# Drop_Screen_OCT_2022_Drivers_1.net
KiCad netlist of a schematic drawn in EasyEDA
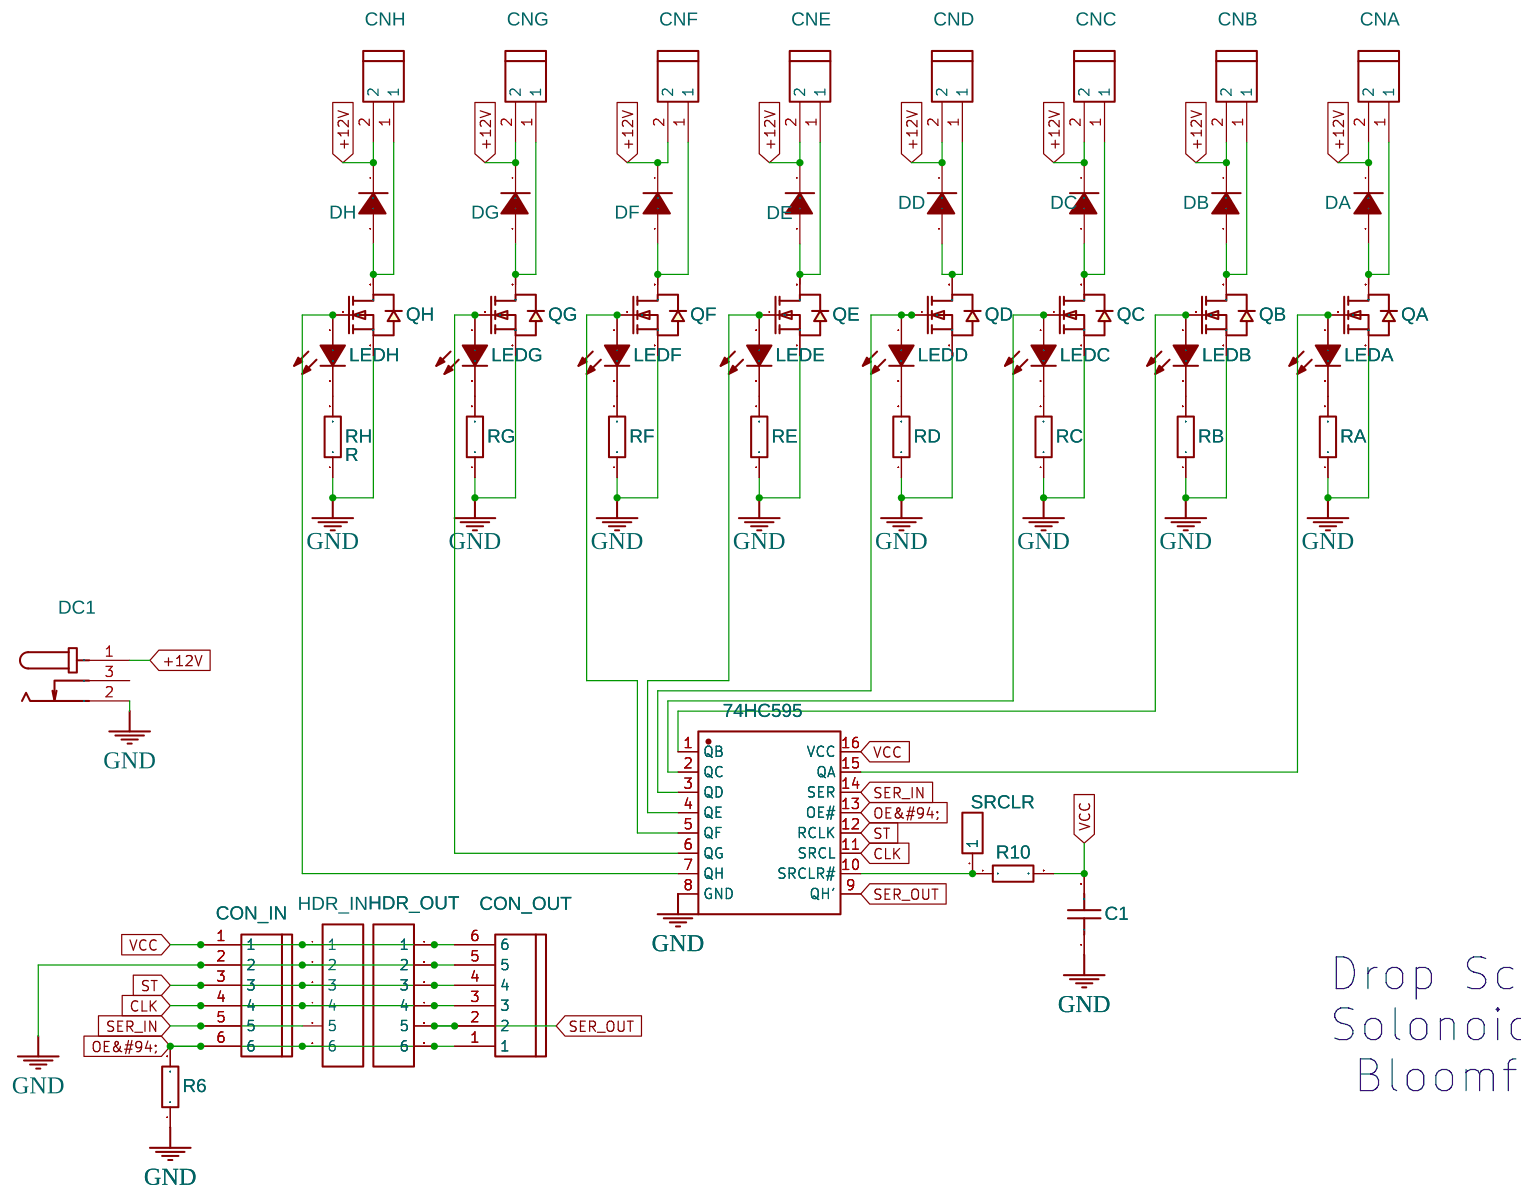
[diagram p0: schematic sheet]

(export (version "E")
  (design (tool "Eeschema 10.0.6"))
  (components
    (comp (ref "C1")
      (value "C")
      (fields
        (field (name "BOM_Manufacturer Part") "CC0603KRX7R7BB104")
        (field (name "BOM_Supplier Part") "C108079")
      )
      (libsource (lib "") (part "CC0603KRX7R7BB104"))
    )
    (comp (ref "CNA")
      (value "CON")
      (fields (field (name "BOM_Manufacturer Part") "XH-2AW") (field (name "BOM_Supplier Part") "C33132"))
      (libsource (lib "") (part "XH-2AW_2"))
    )
    (comp (ref "CNB")
      (value "CON")
      (fields (field (name "BOM_Manufacturer Part") "XH-2AW") (field (name "BOM_Supplier Part") "C33132"))
      (libsource (lib "") (part "XH-2AW_7"))
    )
    (comp (ref "CNC")
      (value "CON")
      (fields (field (name "BOM_Manufacturer Part") "XH-2AW") (field (name "BOM_Supplier Part") "C33132"))
      (libsource (lib "") (part "XH-2AW_5"))
    )
    (comp (ref "CND")
      (value "CON")
      (fields (field (name "BOM_Manufacturer Part") "XH-2AW") (field (name "BOM_Supplier Part") "C33132"))
      (libsource (lib "") (part "XH-2AW_4"))
    )
    (comp (ref "CNE")
      (value "CON")
      (fields (field (name "BOM_Manufacturer Part") "XH-2AW") (field (name "BOM_Supplier Part") "C33132"))
      (libsource (lib "") (part "XH-2AW_6"))
    )
    (comp (ref "CNF")
      (value "CON")
      (fields (field (name "BOM_Manufacturer Part") "XH-2AW") (field (name "BOM_Supplier Part") "C33132"))
      (libsource (lib "") (part "XH-2AW_3"))
    )
    (comp (ref "CNG")
      (value "CON")
      (fields (field (name "BOM_Manufacturer Part") "XH-2AW") (field (name "BOM_Supplier Part") "C33132"))
      (libsource (lib "") (part "XH-2AW_1"))
    )
    (comp (ref "CNH")
      (value "CON")
      (fields (field (name "BOM_Manufacturer Part") "XH-2AW") (field (name "BOM_Supplier Part") "C33132"))
      (libsource (lib "") (part "XH-2AW"))
    )
    (comp (ref "CON_IN")
      (value "CON6")
      (fields (field (name "BOM_Manufacturer Part") "XH-6AW") (field (name "BOM_Supplier Part") "C8876"))
      (libsource (lib "") (part "XH-6AW_C8876_1"))
    )
    (comp (ref "CON_OUT")
      (value "CON6")
      (fields (field (name "BOM_Manufacturer Part") "XH-6AW") (field (name "BOM_Supplier Part") "C8876"))
      (libsource (lib "") (part "XH-6AW_C8876"))
    )
    (comp (ref "DA")
      (value "D")
      (fields (field (name "BOM_Manufacturer Part") "1N4007F") (field (name "BOM_Supplier Part") "C110856"))
      (libsource (lib "") (part "1N4007F_6"))
    )
    (comp (ref "DB")
      (value "D")
      (fields (field (name "BOM_Manufacturer Part") "1N4007F") (field (name "BOM_Supplier Part") "C110856"))
      (libsource (lib "") (part "1N4007F_5"))
    )
    (comp (ref "DC")
      (value "D")
      (fields (field (name "BOM_Manufacturer Part") "1N4007F") (field (name "BOM_Supplier Part") "C110856"))
      (libsource (lib "") (part "1N4007F_7"))
    )
    (comp (ref "DC1")
      (value "DC")
      (fields
        (field (name "BOM_Manufacturer Part") "DC005-2.0MM")
        (field (name "BOM_Supplier Part") "C111567")
      )
      (libsource (lib "") (part "DC005-2.0MM"))
    )
    (comp (ref "DD")
      (value "D")
      (fields (field (name "BOM_Manufacturer Part") "1N4007F") (field (name "BOM_Supplier Part") "C110856"))
      (libsource (lib "") (part "1N4007F_2"))
    )
    (comp (ref "DE")
      (value "D")
      (fields (field (name "BOM_Manufacturer Part") "1N4007F") (field (name "BOM_Supplier Part") "C110856"))
      (libsource (lib "") (part "1N4007F_3"))
    )
    (comp (ref "DF")
      (value "D")
      (fields (field (name "BOM_Manufacturer Part") "1N4007F") (field (name "BOM_Supplier Part") "C110856"))
      (libsource (lib "") (part "1N4007F_4"))
    )
    (comp (ref "DG")
      (value "D")
      (fields (field (name "BOM_Manufacturer Part") "1N4007F") (field (name "BOM_Supplier Part") "C110856"))
      (libsource (lib "") (part "1N4007F"))
    )
    (comp (ref "DH")
      (value "D")
      (fields (field (name "BOM_Manufacturer Part") "1N4007F") (field (name "BOM_Supplier Part") "C110856"))
      (libsource (lib "") (part "1N4007F_1"))
    )
    (comp (ref "HDR_IN")
      (value "HDR6")
      (fields (field (name "BOM_Supplier Part") "C190819"))
      (libsource (lib "") (part "HDR-M-2.54_1x6_1"))
    )
    (comp (ref "HDR_OUT")
      (value "HDR6")
      (fields (field (name "BOM_Supplier Part") "C190819"))
      (libsource (lib "") (part "HDR-M-2.54_1x6"))
    )
    (comp (ref "IC2")
      (value "74HC595")
      (fields
        (field (name "BOM_Manufacturer Part") "U74HC595AG-S16-R")
        (field (name "BOM_Supplier Part") "C87300")
      )
      (libsource (lib "") (part "U74HC595AG-S16-R"))
    )
    (comp (ref "LEDA")
      (value "LED")
      (fields
        (field (name "BOM_Manufacturer Part") "19-217/BHC-ZL1M2RY/3T")
        (field (name "BOM_Supplier Part") "C72041")
      )
      (libsource (lib "") (part "19-217/BHC-ZL1M2RY/3T_7"))
    )
    (comp (ref "LEDB")
      (value "LED")
      (fields
        (field (name "BOM_Manufacturer Part") "19-217/BHC-ZL1M2RY/3T")
        (field (name "BOM_Supplier Part") "C72041")
      )
      (libsource (lib "") (part "19-217/BHC-ZL1M2RY/3T_3"))
    )
    (comp (ref "LEDC")
      (value "LED")
      (fields
        (field (name "BOM_Manufacturer Part") "19-217/BHC-ZL1M2RY/3T")
        (field (name "BOM_Supplier Part") "C72041")
      )
      (libsource (lib "") (part "19-217/BHC-ZL1M2RY/3T_6"))
    )
    (comp (ref "LEDD")
      (value "LED")
      (fields
        (field (name "BOM_Manufacturer Part") "19-217/BHC-ZL1M2RY/3T")
        (field (name "BOM_Supplier Part") "C72041")
      )
      (libsource (lib "") (part "19-217/BHC-ZL1M2RY/3T"))
    )
    (comp (ref "LEDE")
      (value "LED")
      (fields
        (field (name "BOM_Manufacturer Part") "19-217/BHC-ZL1M2RY/3T")
        (field (name "BOM_Supplier Part") "C72041")
      )
      (libsource (lib "") (part "19-217/BHC-ZL1M2RY/3T_1"))
    )
    (comp (ref "LEDF")
      (value "LED")
      (fields
        (field (name "BOM_Manufacturer Part") "19-217/BHC-ZL1M2RY/3T")
        (field (name "BOM_Supplier Part") "C72041")
      )
      (libsource (lib "") (part "19-217/BHC-ZL1M2RY/3T_2"))
    )
    (comp (ref "LEDG")
      (value "LED")
      (fields
        (field (name "BOM_Manufacturer Part") "19-217/BHC-ZL1M2RY/3T")
        (field (name "BOM_Supplier Part") "C72041")
      )
      (libsource (lib "") (part "19-217/BHC-ZL1M2RY/3T_5"))
    )
    (comp (ref "LEDH")
      (value "LED")
      (fields
        (field (name "BOM_Manufacturer Part") "19-217/BHC-ZL1M2RY/3T")
        (field (name "BOM_Supplier Part") "C72041")
      )
      (libsource (lib "") (part "19-217/BHC-ZL1M2RY/3T_4"))
    )
    (comp (ref "QA")
      (value "Q")
      (fields (field (name "BOM_Manufacturer Part") "JSM2302") (field (name "BOM_Supplier Part") "C916403"))
      (libsource (lib "") (part "JSM2302"))
    )
    (comp (ref "QB")
      (value "Q")
      (fields (field (name "BOM_Manufacturer Part") "JSM2302") (field (name "BOM_Supplier Part") "C916403"))
      (libsource (lib "") (part "JSM2302_5"))
    )
    (comp (ref "QC")
      (value "Q")
      (fields (field (name "BOM_Manufacturer Part") "JSM2302") (field (name "BOM_Supplier Part") "C916403"))
      (libsource (lib "") (part "JSM2302_6"))
    )
    (comp (ref "QD")
      (value "Q")
      (fields (field (name "BOM_Manufacturer Part") "JSM2302") (field (name "BOM_Supplier Part") "C916403"))
      (libsource (lib "") (part "JSM2302_1"))
    )
    (comp (ref "QE")
      (value "Q")
      (fields (field (name "BOM_Manufacturer Part") "JSM2302") (field (name "BOM_Supplier Part") "C916403"))
      (libsource (lib "") (part "JSM2302_2"))
    )
    (comp (ref "QF")
      (value "Q")
      (fields (field (name "BOM_Manufacturer Part") "JSM2302") (field (name "BOM_Supplier Part") "C916403"))
      (libsource (lib "") (part "JSM2302_4"))
    )
    (comp (ref "QG")
      (value "Q")
      (fields (field (name "BOM_Manufacturer Part") "JSM2302") (field (name "BOM_Supplier Part") "C916403"))
      (libsource (lib "") (part "JSM2302_3"))
    )
    (comp (ref "QH")
      (value "Q")
      (fields (field (name "BOM_Manufacturer Part") "JSM2302") (field (name "BOM_Supplier Part") "C916403"))
      (libsource (lib "") (part "JSM2302_7"))
    )
    (comp (ref "R6")
      (value "R")
      (fields
        (field (name "BOM_Manufacturer Part") "0603WAF1001T5E")
        (field (name "BOM_Supplier Part") "C21190")
      )
      (libsource (lib "") (part "0603WAF1001T5E_1"))
    )
    (comp (ref "R10")
      (value "R")
      (fields
        (field (name "BOM_Manufacturer Part") "0603WAF1001T5E")
        (field (name "BOM_Supplier Part") "C21190")
      )
      (libsource (lib "") (part "0603WAF1001T5E_9"))
    )
    (comp (ref "RA")
      (value "R")
      (fields
        (field (name "BOM_Manufacturer Part") "0603WAF1001T5E")
        (field (name "BOM_Supplier Part") "C21190")
      )
      (libsource (lib "") (part "0603WAF1001T5E_7"))
    )
    (comp (ref "RB")
      (value "R")
      (fields
        (field (name "BOM_Manufacturer Part") "0603WAF1001T5E")
        (field (name "BOM_Supplier Part") "C21190")
      )
      (libsource (lib "") (part "0603WAF1001T5E"))
    )
    (comp (ref "RC")
      (value "R")
      (fields
        (field (name "BOM_Manufacturer Part") "0603WAF1001T5E")
        (field (name "BOM_Supplier Part") "C21190")
      )
      (libsource (lib "") (part "0603WAF1001T5E_5"))
    )
    (comp (ref "RD")
      (value "R")
      (fields
        (field (name "BOM_Manufacturer Part") "0603WAF1001T5E")
        (field (name "BOM_Supplier Part") "C21190")
      )
      (libsource (lib "") (part "0603WAF1001T5E_6"))
    )
    (comp (ref "RE")
      (value "R")
      (fields
        (field (name "BOM_Manufacturer Part") "0603WAF1001T5E")
        (field (name "BOM_Supplier Part") "C21190")
      )
      (libsource (lib "") (part "0603WAF1001T5E_3"))
    )
    (comp (ref "RF")
      (value "R")
      (fields
        (field (name "BOM_Manufacturer Part") "0603WAF1001T5E")
        (field (name "BOM_Supplier Part") "C21190")
      )
      (libsource (lib "") (part "0603WAF1001T5E_4"))
    )
    (comp (ref "RG")
      (value "R")
      (fields
        (field (name "BOM_Manufacturer Part") "0603WAF1001T5E")
        (field (name "BOM_Supplier Part") "C21190")
      )
      (libsource (lib "") (part "0603WAF1001T5E_8"))
    )
    (comp (ref "RH")
      (value "R")
      (fields
        (field (name "BOM_Manufacturer Part") "0603WAF1001T5E")
        (field (name "BOM_Supplier Part") "C21190")
      )
      (libsource (lib "") (part "0603WAF1001T5E_2"))
    )
    (comp (ref "SRCLR")
      (value "HDR-M-2.54_1x1")
      (fields (field (name "BOM_Supplier Part") "C81276"))
      (libsource (lib "") (part "HDR-M-2.54_1x1"))
    )
  )
  (nets
    (net (code "1") (name "+12V") (class "Default")
      (node (ref "CNA") (pin "2") (pinfunction "2_2") (pintype "unspecified"))
      (node (ref "CNB") (pin "2") (pinfunction "2_2") (pintype "unspecified"))
      (node (ref "CNC") (pin "2") (pinfunction "2_2") (pintype "unspecified"))
      (node (ref "CND") (pin "2") (pinfunction "2_2") (pintype "unspecified"))
      (node (ref "CNE") (pin "2") (pinfunction "2_2") (pintype "unspecified"))
      (node (ref "CNF") (pin "2") (pinfunction "2_2") (pintype "unspecified"))
      (node (ref "CNG") (pin "2") (pinfunction "2_2") (pintype "unspecified"))
      (node (ref "CNH") (pin "2") (pinfunction "2_2") (pintype "unspecified"))
      (node (ref "DA") (pin "1") (pinfunction "C_1") (pintype "unspecified"))
      (node (ref "DB") (pin "1") (pinfunction "C_1") (pintype "unspecified"))
      (node (ref "DC") (pin "1") (pinfunction "C_1") (pintype "unspecified"))
      (node (ref "DC1") (pin "1") (pinfunction "1_1") (pintype "unspecified"))
      (node (ref "DD") (pin "1") (pinfunction "C_1") (pintype "unspecified"))
      (node (ref "DE") (pin "1") (pinfunction "C_1") (pintype "unspecified"))
      (node (ref "DF") (pin "1") (pinfunction "C_1") (pintype "unspecified"))
      (node (ref "DG") (pin "1") (pinfunction "C_1") (pintype "unspecified"))
      (node (ref "DH") (pin "1") (pinfunction "C_1") (pintype "unspecified"))
    )
    (net (code "2") (name "CLK") (class "Default")
      (node (ref "CON_IN") (pin "4") (pinfunction "4_4") (pintype "unspecified"))
      (node (ref "CON_OUT") (pin "3") (pinfunction "3_3") (pintype "unspecified"))
      (node (ref "HDR_IN") (pin "4") (pinfunction "4_4") (pintype "input"))
      (node (ref "HDR_OUT") (pin "4") (pinfunction "4_4") (pintype "input"))
      (node (ref "IC2") (pin "11") (pinfunction "SRCL_11") (pintype "unspecified"))
    )
    (net (code "3") (name "GND") (class "Default")
      (node (ref "C1") (pin "1") (pinfunction "1_1") (pintype "unspecified"))
      (node (ref "CON_IN") (pin "2") (pinfunction "2_2") (pintype "unspecified"))
      (node (ref "CON_OUT") (pin "5") (pinfunction "5_5") (pintype "unspecified"))
      (node (ref "DC1") (pin "2") (pinfunction "2_2") (pintype "unspecified"))
      (node (ref "HDR_IN") (pin "2") (pinfunction "2_2") (pintype "input"))
      (node (ref "HDR_OUT") (pin "2") (pinfunction "2_2") (pintype "input"))
      (node (ref "IC2") (pin "8") (pinfunction "GND_8") (pintype "unspecified"))
      (node (ref "QA") (pin "2") (pinfunction "S_2") (pintype "unspecified"))
      (node (ref "QB") (pin "2") (pinfunction "S_2") (pintype "unspecified"))
      (node (ref "QC") (pin "2") (pinfunction "S_2") (pintype "unspecified"))
      (node (ref "QD") (pin "2") (pinfunction "S_2") (pintype "unspecified"))
      (node (ref "QE") (pin "2") (pinfunction "S_2") (pintype "unspecified"))
      (node (ref "QF") (pin "2") (pinfunction "S_2") (pintype "unspecified"))
      (node (ref "QG") (pin "2") (pinfunction "S_2") (pintype "unspecified"))
      (node (ref "QH") (pin "2") (pinfunction "S_2") (pintype "unspecified"))
      (node (ref "R6") (pin "1") (pinfunction "1_1") (pintype "input"))
      (node (ref "RA") (pin "1") (pinfunction "1_1") (pintype "input"))
      (node (ref "RB") (pin "1") (pinfunction "1_1") (pintype "input"))
      (node (ref "RC") (pin "1") (pinfunction "1_1") (pintype "input"))
      (node (ref "RD") (pin "1") (pinfunction "1_1") (pintype "input"))
      (node (ref "RE") (pin "1") (pinfunction "1_1") (pintype "input"))
      (node (ref "RF") (pin "1") (pinfunction "1_1") (pintype "input"))
      (node (ref "RG") (pin "1") (pinfunction "1_1") (pintype "input"))
      (node (ref "RH") (pin "1") (pinfunction "1_1") (pintype "input"))
    )
    (net (code "4") (name "Net-(DA-A)") (class "Default")
      (node (ref "CNA") (pin "1") (pinfunction "1_1") (pintype "unspecified"))
      (node (ref "DA") (pin "2") (pinfunction "A_2") (pintype "unspecified"))
      (node (ref "QA") (pin "3") (pinfunction "D_3") (pintype "unspecified"))
    )
    (net (code "5") (name "Net-(DB-A)") (class "Default")
      (node (ref "CNB") (pin "1") (pinfunction "1_1") (pintype "unspecified"))
      (node (ref "DB") (pin "2") (pinfunction "A_2") (pintype "unspecified"))
      (node (ref "QB") (pin "3") (pinfunction "D_3") (pintype "unspecified"))
    )
    (net (code "6") (name "Net-(DC-A)") (class "Default")
      (node (ref "CNC") (pin "1") (pinfunction "1_1") (pintype "unspecified"))
      (node (ref "DC") (pin "2") (pinfunction "A_2") (pintype "unspecified"))
      (node (ref "QC") (pin "3") (pinfunction "D_3") (pintype "unspecified"))
    )
    (net (code "7") (name "Net-(DD-A)") (class "Default")
      (node (ref "CND") (pin "1") (pinfunction "1_1") (pintype "unspecified"))
      (node (ref "DD") (pin "2") (pinfunction "A_2") (pintype "unspecified"))
      (node (ref "QD") (pin "3") (pinfunction "D_3") (pintype "unspecified"))
    )
    (net (code "8") (name "Net-(DE-A)") (class "Default")
      (node (ref "CNE") (pin "1") (pinfunction "1_1") (pintype "unspecified"))
      (node (ref "DE") (pin "2") (pinfunction "A_2") (pintype "unspecified"))
      (node (ref "QE") (pin "3") (pinfunction "D_3") (pintype "unspecified"))
    )
    (net (code "9") (name "Net-(DF-A)") (class "Default")
      (node (ref "CNF") (pin "1") (pinfunction "1_1") (pintype "unspecified"))
      (node (ref "DF") (pin "2") (pinfunction "A_2") (pintype "unspecified"))
      (node (ref "QF") (pin "3") (pinfunction "D_3") (pintype "unspecified"))
    )
    (net (code "10") (name "Net-(DG-A)") (class "Default")
      (node (ref "CNG") (pin "1") (pinfunction "1_1") (pintype "unspecified"))
      (node (ref "DG") (pin "2") (pinfunction "A_2") (pintype "unspecified"))
      (node (ref "QG") (pin "3") (pinfunction "D_3") (pintype "unspecified"))
    )
    (net (code "11") (name "Net-(DH-A)") (class "Default")
      (node (ref "CNH") (pin "1") (pinfunction "1_1") (pintype "unspecified"))
      (node (ref "DH") (pin "2") (pinfunction "A_2") (pintype "unspecified"))
      (node (ref "QH") (pin "3") (pinfunction "D_3") (pintype "unspecified"))
    )
    (net (code "12") (name "Net-(IC2-QA)") (class "Default")
      (node (ref "IC2") (pin "15") (pinfunction "QA_15") (pintype "unspecified"))
      (node (ref "LEDA") (pin "1") (pinfunction "A_1") (pintype "input"))
      (node (ref "QA") (pin "1") (pinfunction "G_1") (pintype "unspecified"))
    )
    (net (code "13") (name "Net-(IC2-QB)") (class "Default")
      (node (ref "IC2") (pin "1") (pinfunction "QB_1") (pintype "unspecified"))
      (node (ref "LEDB") (pin "1") (pinfunction "A_1") (pintype "input"))
      (node (ref "QB") (pin "1") (pinfunction "G_1") (pintype "unspecified"))
    )
    (net (code "14") (name "Net-(IC2-QC)") (class "Default")
      (node (ref "IC2") (pin "2") (pinfunction "QC_2") (pintype "unspecified"))
      (node (ref "LEDC") (pin "1") (pinfunction "A_1") (pintype "input"))
      (node (ref "QC") (pin "1") (pinfunction "G_1") (pintype "unspecified"))
    )
    (net (code "15") (name "Net-(IC2-QD)") (class "Default")
      (node (ref "IC2") (pin "3") (pinfunction "QD_3") (pintype "unspecified"))
      (node (ref "LEDD") (pin "1") (pinfunction "A_1") (pintype "input"))
      (node (ref "QD") (pin "1") (pinfunction "G_1") (pintype "unspecified"))
    )
    (net (code "16") (name "Net-(IC2-QE)") (class "Default")
      (node (ref "IC2") (pin "4") (pinfunction "QE_4") (pintype "unspecified"))
      (node (ref "LEDE") (pin "1") (pinfunction "A_1") (pintype "input"))
      (node (ref "QE") (pin "1") (pinfunction "G_1") (pintype "unspecified"))
    )
    (net (code "17") (name "Net-(IC2-QF)") (class "Default")
      (node (ref "IC2") (pin "5") (pinfunction "QF_5") (pintype "unspecified"))
      (node (ref "LEDF") (pin "1") (pinfunction "A_1") (pintype "input"))
      (node (ref "QF") (pin "1") (pinfunction "G_1") (pintype "unspecified"))
    )
    (net (code "18") (name "Net-(IC2-QG)") (class "Default")
      (node (ref "IC2") (pin "6") (pinfunction "QG_6") (pintype "unspecified"))
      (node (ref "LEDG") (pin "1") (pinfunction "A_1") (pintype "input"))
      (node (ref "QG") (pin "1") (pinfunction "G_1") (pintype "unspecified"))
    )
    (net (code "19") (name "Net-(IC2-QH)") (class "Default")
      (node (ref "IC2") (pin "7") (pinfunction "QH_7") (pintype "unspecified"))
      (node (ref "LEDH") (pin "1") (pinfunction "A_1") (pintype "input"))
      (node (ref "QH") (pin "1") (pinfunction "G_1") (pintype "unspecified"))
    )
    (net (code "20") (name "Net-(IC2-SRCLR#)") (class "Default")
      (node (ref "IC2") (pin "10") (pinfunction "SRCLR#_10") (pintype "unspecified"))
      (node (ref "R10") (pin "1") (pinfunction "1_1") (pintype "input"))
      (node (ref "SRCLR") (pin "1") (pinfunction "1_1") (pintype "input"))
    )
    (net (code "21") (name "Net-(LEDA-C)") (class "Default")
      (node (ref "LEDA") (pin "2") (pinfunction "C_2") (pintype "input"))
      (node (ref "RA") (pin "2") (pinfunction "2_2") (pintype "input"))
    )
    (net (code "22") (name "Net-(LEDB-C)") (class "Default")
      (node (ref "LEDB") (pin "2") (pinfunction "C_2") (pintype "input"))
      (node (ref "RB") (pin "2") (pinfunction "2_2") (pintype "input"))
    )
    (net (code "23") (name "Net-(LEDC-C)") (class "Default")
      (node (ref "LEDC") (pin "2") (pinfunction "C_2") (pintype "input"))
      (node (ref "RC") (pin "2") (pinfunction "2_2") (pintype "input"))
    )
    (net (code "24") (name "Net-(LEDD-C)") (class "Default")
      (node (ref "LEDD") (pin "2") (pinfunction "C_2") (pintype "input"))
      (node (ref "RD") (pin "2") (pinfunction "2_2") (pintype "input"))
    )
    (net (code "25") (name "Net-(LEDE-C)") (class "Default")
      (node (ref "LEDE") (pin "2") (pinfunction "C_2") (pintype "input"))
      (node (ref "RE") (pin "2") (pinfunction "2_2") (pintype "input"))
    )
    (net (code "26") (name "Net-(LEDF-C)") (class "Default")
      (node (ref "LEDF") (pin "2") (pinfunction "C_2") (pintype "input"))
      (node (ref "RF") (pin "2") (pinfunction "2_2") (pintype "input"))
    )
    (net (code "27") (name "Net-(LEDG-C)") (class "Default")
      (node (ref "LEDG") (pin "2") (pinfunction "C_2") (pintype "input"))
      (node (ref "RG") (pin "2") (pinfunction "2_2") (pintype "input"))
    )
    (net (code "28") (name "Net-(LEDH-C)") (class "Default")
      (node (ref "LEDH") (pin "2") (pinfunction "C_2") (pintype "input"))
      (node (ref "RH") (pin "2") (pinfunction "2_2") (pintype "input"))
    )
    (net (code "29") (name "OE&#94;") (class "Default")
      (node (ref "CON_IN") (pin "6") (pinfunction "6_6") (pintype "unspecified"))
      (node (ref "CON_OUT") (pin "1") (pinfunction "1_1") (pintype "unspecified"))
      (node (ref "HDR_IN") (pin "6") (pinfunction "6_6") (pintype "input"))
      (node (ref "HDR_OUT") (pin "6") (pinfunction "6_6") (pintype "input"))
      (node (ref "IC2") (pin "13") (pinfunction "OE#_13") (pintype "unspecified"))
      (node (ref "R6") (pin "2") (pinfunction "2_2") (pintype "input"))
    )
    (net (code "30") (name "SER_IN") (class "Default")
      (node (ref "CON_IN") (pin "5") (pinfunction "5_5") (pintype "unspecified"))
      (node (ref "HDR_IN") (pin "5") (pinfunction "5_5") (pintype "input"))
      (node (ref "IC2") (pin "14") (pinfunction "SER_14") (pintype "unspecified"))
    )
    (net (code "31") (name "SER_OUT") (class "Default")
      (node (ref "CON_OUT") (pin "2") (pinfunction "2_2") (pintype "unspecified"))
      (node (ref "HDR_OUT") (pin "5") (pinfunction "5_5") (pintype "input"))
      (node (ref "IC2") (pin "9") (pinfunction "QH'_9") (pintype "unspecified"))
    )
    (net (code "32") (name "ST") (class "Default")
      (node (ref "CON_IN") (pin "3") (pinfunction "3_3") (pintype "unspecified"))
      (node (ref "CON_OUT") (pin "4") (pinfunction "4_4") (pintype "unspecified"))
      (node (ref "HDR_IN") (pin "3") (pinfunction "3_3") (pintype "input"))
      (node (ref "HDR_OUT") (pin "3") (pinfunction "3_3") (pintype "input"))
      (node (ref "IC2") (pin "12") (pinfunction "RCLK_12") (pintype "unspecified"))
    )
    (net (code "33") (name "VCC") (class "Default")
      (node (ref "C1") (pin "2") (pinfunction "2_2") (pintype "unspecified"))
      (node (ref "CON_IN") (pin "1") (pinfunction "1_1") (pintype "unspecified"))
      (node (ref "CON_OUT") (pin "6") (pinfunction "6_6") (pintype "unspecified"))
      (node (ref "HDR_IN") (pin "1") (pinfunction "1_1") (pintype "input"))
      (node (ref "HDR_OUT") (pin "1") (pinfunction "1_1") (pintype "input"))
      (node (ref "IC2") (pin "16") (pinfunction "VCC_16") (pintype "unspecified"))
      (node (ref "R10") (pin "2") (pinfunction "2_2") (pintype "input"))
    )
    (net (code "34") (name "unconnected-(DC1-Pad3)") (class "Default")
      (node (ref "DC1") (pin "3") (pinfunction "3_3") (pintype "unspecified"))
    )
  )
)
